# MagController.net
KiCad netlist of a schematic drawn in Altium Designer
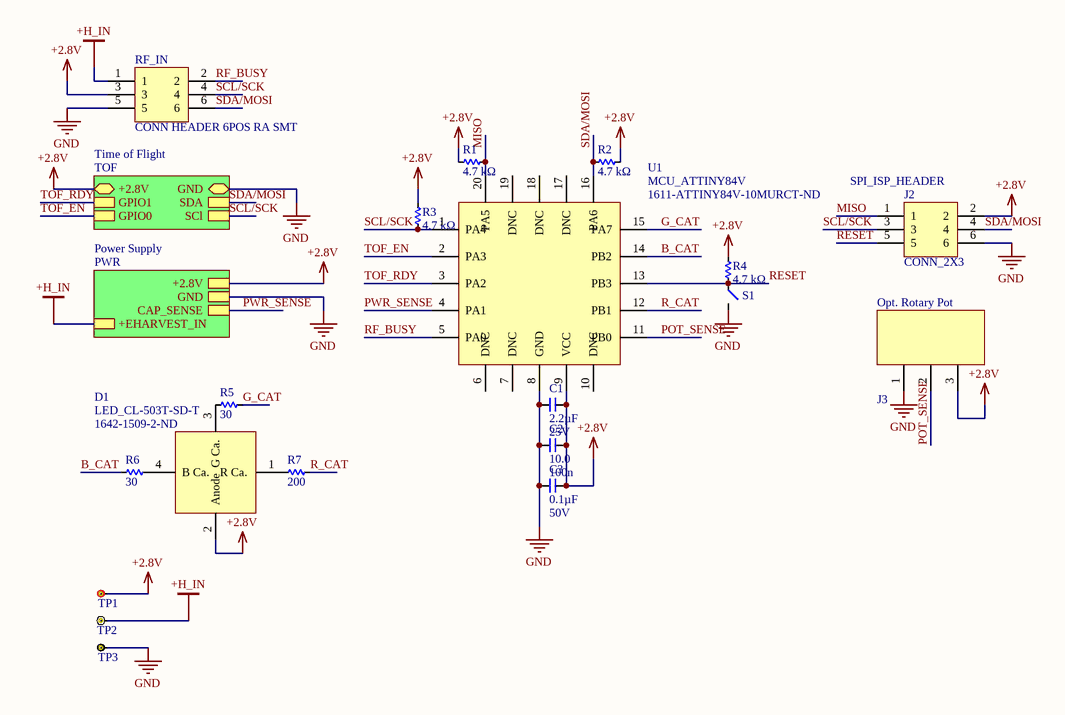
[diagram p0: MagController.SchDoc]

(export (version "E")
  (design (tool "Eeschema 10.0.6"))
  (components
    (comp (ref "C1")
      (value "__template_cap")
      (footprint "C0603")
      (fields
        (field (name "CAPACITANCE (SHORTHAND)") "2.2µF")
        (field (name "RATED VOLTAGE") "25V")
        (field (name "MANUFACTURER") "Murata Electronics North America")
      )
      (libsource (lib "passives") (part "__template_cap"))
    )
    (comp (ref "C2")
      (value "399-3520-1-ND")
      (footprint "C0402")
      (fields
        (field (name "VOLTAGE") "10.0")
        (field (name "HUMAN_VALUE") "100n")
        (field (name "TOLERANCE") "10%")
      )
      (libsource (lib "sscp") (part "__template_cap"))
    )
    (comp (ref "C3")
      (value "__template_cap")
      (footprint "C0805")
      (fields
        (field (name "CAPACITANCE (SHORTHAND)") "0.1µF")
        (field (name "RATED VOLTAGE") "50V")
        (field (name "MANUFACTURER") "Murata Electronics North America")
      )
      (libsource (lib "passives") (part "__template_cap"))
    )
    (comp (ref "D1")
      (value "LED_CL-503T-SD-T")
      (footprint "LED_RGB_CL-503T-SD-T")
      (description "RGB LOW VOLTAGE RICOLOR TOP FIRING 1.5 X 1.3 X")
      (fields
        (field (name "MANUFACTURER") "Citizen")
        (field (name "MANUFACTURER PART NUMBER") "CL-503T-SD-T")
        (field (name "SUPPLIER PART NUMBER 1") "1642-1509-2-ND")
      )
      (libsource (lib "SSI") (part "LED_CL-503T-SD-T"))
    )
    (comp (ref "J2")
      (value "CONN_2X3")
      (footprint "CONN_2x3_100MIL")
      (libsource (lib "SSI") (part "CONN_2X3"))
    )
    (comp (ref "J3")
      (value "CONN_1x3_640454-3")
      (footprint "CONN_1x3_100MIL")
      (description "CONN HEADER VERT 3POS .100 TIN")
      (fields
        (field (name "MANUFACTURER") "TE Connectivity")
        (field (name "MANUFACTURER PART NUMBER") "640454-3")
      )
      (libsource (lib "SSI") (part "CONN_1x3_640454-3"))
    )
    (comp (ref "R1")
      (value "__template_resistor")
      (footprint "R0805")
      (fields
        (field (name "RESISTANCE") "4.7 kΩ")
        (field (name "MANUFACTURER PART NUMBER") "RC0805FR-074K7L")
        (field (name "MANUFACTURER") "Yageo")
        (field (name "TOLERANCE") "±1%")
      )
      (libsource (lib "passives") (part "__template_resistor"))
    )
    (comp (ref "R2")
      (value "__template_resistor")
      (footprint "R0805")
      (fields
        (field (name "RESISTANCE") "4.7 kΩ")
        (field (name "MANUFACTURER PART NUMBER") "RC0805FR-074K7L")
        (field (name "MANUFACTURER") "Yageo")
        (field (name "TOLERANCE") "±1%")
      )
      (libsource (lib "passives") (part "__template_resistor"))
    )
    (comp (ref "R3")
      (value "__template_resistor")
      (footprint "R0805")
      (fields
        (field (name "RESISTANCE") "4.7 kΩ")
        (field (name "MANUFACTURER PART NUMBER") "RC0805FR-074K7L")
        (field (name "MANUFACTURER") "Yageo")
        (field (name "TOLERANCE") "±1%")
      )
      (libsource (lib "passives") (part "__template_resistor"))
    )
    (comp (ref "R4")
      (value "__template_resistor")
      (footprint "R0805")
      (fields
        (field (name "RESISTANCE") "4.7 kΩ")
        (field (name "MANUFACTURER PART NUMBER") "RC0805FR-074K7L")
        (field (name "MANUFACTURER") "Yageo")
        (field (name "TOLERANCE") "±1%")
      )
      (libsource (lib "passives") (part "__template_resistor"))
    )
    (comp (ref "R5")
      (value "30")
      (footprint "R1206")
      (fields
        (field (name "MANUFACTURER PART NUMBER") "CRCW120630R0FKEA")
        (field (name "MANUFACTURER") "Vishay Dale")
        (field (name "TOLERANCE") "±1%")
      )
      (libsource (lib "resistor") (part "__template_resistor"))
    )
    (comp (ref "R6")
      (value "30")
      (footprint "R1206")
      (fields
        (field (name "MANUFACTURER PART NUMBER") "CRCW120630R0FKEA")
        (field (name "MANUFACTURER") "Vishay Dale")
        (field (name "TOLERANCE") "±1%")
      )
      (libsource (lib "resistor") (part "__template_resistor"))
    )
    (comp (ref "R7")
      (value "200")
      (footprint "R1206")
      (fields
        (field (name "MANUFACTURER PART NUMBER") "CRCW1206200RFKEA")
        (field (name "MANUFACTURER") "Vishay Dale")
        (field (name "TOLERANCE") "±1%")
      )
      (libsource (lib "resistor") (part "__template_resistor"))
    )
    (comp (ref "RF_IN")
      (value "CONN HEADER 6POS RA SMT")
      (footprint "CONN_2x3_100MIL")
      (libsource (lib "SSI") (part "CONN_2X3"))
    )
    (comp (ref "S1")
      (value "B3U-1000P")
      (footprint "SWITCH_B3U-1000P")
      (description "SWITCH TACTILE SPST-NO 0.05A 12V")
      (fields (field (name "MANUFACTURER") "Omron Electronics Inc-EMC Div"))
      (libsource (lib "SSI") (part "SWITCH_SPST-NO"))
    )
    (comp (ref "TP1")
      (value "TEST_POINT_RED_KEYSTONE_5000")
      (footprint "TEST_POINT_KEYSTONE_5000")
      (description "RED T/H TEST POINT")
      (fields
        (field (name "MANUFACTURER") "Keystone Electronics")
        (field (name "MANUFACTURER PART NUMBER") "5000")
      )
      (libsource (lib "SSI") (part "TEST_POINT_RED_KEYSTONE_5000"))
    )
    (comp (ref "TP2")
      (value "TEST_POINT_WHITE_KEYSTONE_5002")
      (footprint "TEST_POINT_KEYSTONE_5002")
      (description "WHITE T/H TEST POINT")
      (fields
        (field (name "MANUFACTURER") "Keystone Electronics")
        (field (name "MANUFACTURER PART NUMBER") "5002")
      )
      (libsource (lib "SSI") (part "TEST_POINT_WHITE_KEYSTONE_5002"))
    )
    (comp (ref "TP3")
      (value "TEST_POINT_BLACK_KEYSTONE_5001")
      (footprint "TEST_POINT_KEYSTONE_5001")
      (description "BLACK T/H TEST POINT")
      (fields
        (field (name "MANUFACTURER") "Keystone Electronics")
        (field (name "MANUFACTURER PART NUMBER") "5001")
      )
      (libsource (lib "SSI") (part "TEST_POINT_BLACK_KEYSTONE_5001"))
    )
    (comp (ref "U1")
      (value "MCU_ATTINY84V")
      (footprint "20QFN4")
      (description "Attiny84 Surface Mount Extended Voltage Range")
      (fields
        (field (name "MANUFACTURER") "Microchip Technology")
        (field (name "MANUFACTURER PART NUMBER") "ATTINY84V-10MUR")
        (field (name "SUPPLIER PART NUMBER 1") "1611-ATTINY84V-10MURCT-ND")
      )
      (libsource (lib "SSI") (part "MCU_ATTINY84V"))
    )
  )
  (nets
    (net (code "1") (name "+2.8V") (class "Default")
      (node (ref "C1") (pin "2") (pintype "passive"))
      (node (ref "C2") (pin "2") (pintype "passive"))
      (node (ref "C3") (pin "2") (pintype "passive"))
      (node (ref "D1") (pin "2") (pinfunction "Anode_2") (pintype "power_in"))
      (node (ref "J2") (pin "2") (pinfunction "2_2") (pintype "passive"))
      (node (ref "J3") (pin "3") (pinfunction "3_3") (pintype "passive"))
      (node (ref "R1") (pin "2") (pintype "passive"))
      (node (ref "R2") (pin "2") (pintype "passive"))
      (node (ref "R3") (pin "2") (pintype "passive"))
      (node (ref "R4") (pin "2") (pintype "passive"))
      (node (ref "RF_IN") (pin "3") (pinfunction "3_3") (pintype "passive"))
      (node (ref "TP1") (pin "1") (pinfunction "1_1") (pintype "passive"))
      (node (ref "U1") (pin "9") (pinfunction "VCC_9") (pintype "power_in"))
    )
    (net (code "2") (name "+H_IN") (class "Default")
      (node (ref "RF_IN") (pin "1") (pinfunction "1_1") (pintype "passive"))
      (node (ref "TP2") (pin "1") (pinfunction "1_1") (pintype "passive"))
    )
    (net (code "3") (name "/B_CAT") (class "Default")
      (node (ref "R6") (pin "2") (pintype "passive"))
      (node (ref "U1") (pin "14") (pinfunction "PB2_14") (pintype "power_in"))
    )
    (net (code "4") (name "/G_CAT") (class "Default")
      (node (ref "R5") (pin "2") (pintype "passive"))
      (node (ref "U1") (pin "15") (pinfunction "PA7_15") (pintype "power_in"))
    )
    (net (code "5") (name "/MISO") (class "Default")
      (node (ref "J2") (pin "1") (pinfunction "1_1") (pintype "passive"))
      (node (ref "R1") (pin "1") (pintype "passive"))
      (node (ref "U1") (pin "20") (pinfunction "PA5_20") (pintype "power_in"))
    )
    (net (code "6") (name "/POT_SENSE") (class "Default")
      (node (ref "J3") (pin "2") (pinfunction "2_2") (pintype "passive"))
      (node (ref "U1") (pin "11") (pinfunction "PB0_11") (pintype "power_in"))
    )
    (net (code "7") (name "/PWR_SENSE") (class "Default")
      (node (ref "U1") (pin "4") (pinfunction "PA1_4") (pintype "power_in"))
    )
    (net (code "8") (name "/RESET") (class "Default")
      (node (ref "J2") (pin "5") (pinfunction "5_5") (pintype "passive"))
      (node (ref "R4") (pin "1") (pintype "passive"))
      (node (ref "S1") (pin "1") (pintype "passive"))
      (node (ref "U1") (pin "13") (pinfunction "PB3_13") (pintype "power_in"))
    )
    (net (code "9") (name "/RF_BUSY") (class "Default")
      (node (ref "RF_IN") (pin "2") (pinfunction "2_2") (pintype "passive"))
      (node (ref "U1") (pin "5") (pinfunction "PA0_5") (pintype "power_in"))
    )
    (net (code "10") (name "/R_CAT") (class "Default")
      (node (ref "R7") (pin "2") (pintype "passive"))
      (node (ref "U1") (pin "12") (pinfunction "PB1_12") (pintype "power_in"))
    )
    (net (code "11") (name "/SCL{slash}SCK") (class "Default")
      (node (ref "J2") (pin "3") (pinfunction "3_3") (pintype "passive"))
      (node (ref "R3") (pin "1") (pintype "passive"))
      (node (ref "RF_IN") (pin "4") (pinfunction "4_4") (pintype "passive"))
      (node (ref "U1") (pin "1") (pinfunction "PA4_1") (pintype "power_in"))
    )
    (net (code "12") (name "/SDA{slash}MOSI") (class "Default")
      (node (ref "J2") (pin "4") (pinfunction "4_4") (pintype "passive"))
      (node (ref "R2") (pin "1") (pintype "passive"))
      (node (ref "RF_IN") (pin "6") (pinfunction "6_6") (pintype "passive"))
      (node (ref "U1") (pin "16") (pinfunction "PA6_16") (pintype "power_in"))
    )
    (net (code "13") (name "/TOF_EN") (class "Default")
      (node (ref "U1") (pin "2") (pinfunction "PA3_2") (pintype "power_in"))
    )
    (net (code "14") (name "/TOF_RDY") (class "Default")
      (node (ref "U1") (pin "3") (pinfunction "PA2_3") (pintype "power_in"))
    )
    (net (code "15") (name "GND") (class "Default")
      (node (ref "C1") (pin "1") (pintype "passive"))
      (node (ref "C2") (pin "1") (pintype "passive"))
      (node (ref "C3") (pin "1") (pintype "passive"))
      (node (ref "J2") (pin "6") (pinfunction "6_6") (pintype "passive"))
      (node (ref "J3") (pin "1") (pinfunction "1_1") (pintype "passive"))
      (node (ref "RF_IN") (pin "5") (pinfunction "5_5") (pintype "passive"))
      (node (ref "S1") (pin "2") (pintype "passive"))
      (node (ref "TP3") (pin "1") (pinfunction "1_1") (pintype "passive"))
      (node (ref "U1") (pin "8") (pinfunction "GND_8") (pintype "power_in"))
    )
    (net (code "16") (name "Net-(D1-B_Ca.)") (class "Default")
      (node (ref "D1") (pin "4") (pinfunction "B_Ca._4") (pintype "power_in"))
      (node (ref "R6") (pin "1") (pintype "passive"))
    )
    (net (code "17") (name "Net-(D1-G_Ca.)") (class "Default")
      (node (ref "D1") (pin "3") (pinfunction "G_Ca._3") (pintype "power_in"))
      (node (ref "R5") (pin "1") (pintype "passive"))
    )
    (net (code "18") (name "Net-(D1-R_Ca.)") (class "Default")
      (node (ref "D1") (pin "1") (pinfunction "R_Ca._1") (pintype "power_in"))
      (node (ref "R7") (pin "1") (pintype "passive"))
    )
    (net (code "19") (name "unconnected-(U1-DNC-Pad6)") (class "Default")
      (node (ref "U1") (pin "6") (pinfunction "DNC_6") (pintype "power_in"))
    )
    (net (code "20") (name "unconnected-(U1-DNC-Pad7)") (class "Default")
      (node (ref "U1") (pin "7") (pinfunction "DNC_7") (pintype "power_in"))
    )
    (net (code "21") (name "unconnected-(U1-DNC-Pad10)") (class "Default")
      (node (ref "U1") (pin "10") (pinfunction "DNC_10") (pintype "power_in"))
    )
    (net (code "22") (name "unconnected-(U1-DNC-Pad17)") (class "Default")
      (node (ref "U1") (pin "17") (pinfunction "DNC_17") (pintype "power_in"))
    )
    (net (code "23") (name "unconnected-(U1-DNC-Pad18)") (class "Default")
      (node (ref "U1") (pin "18") (pinfunction "DNC_18") (pintype "power_in"))
    )
    (net (code "24") (name "unconnected-(U1-DNC-Pad19)") (class "Default")
      (node (ref "U1") (pin "19") (pinfunction "DNC_19") (pintype "power_in"))
    )
  )
)
